# Microcontroller.net
KiCad netlist of a schematic drawn in Altium Designer
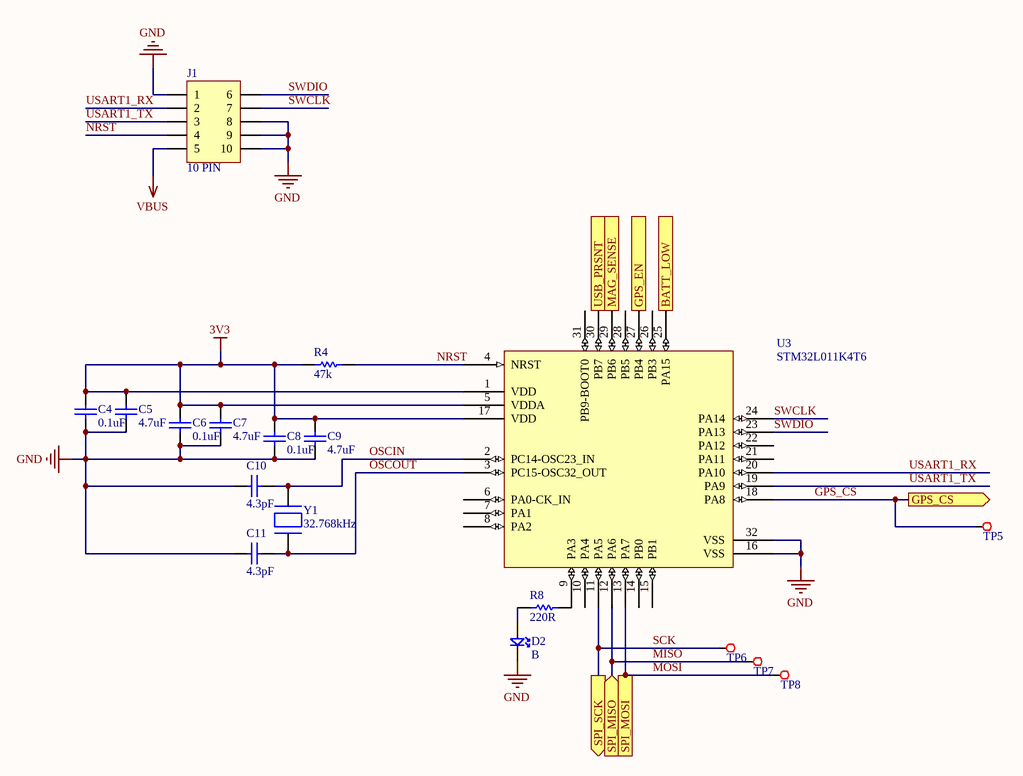
[diagram p0: Microcontroller.SchDoc]

(export (version "E")
  (design (tool "Eeschema 10.0.6"))
  (components
    (comp (ref "C4")
      (value "0.1uF")
      (footprint "0603CAP")
      (description "0603 Ceramic Chip Capacitor - Standard")
      (fields (field (name "Comment") "C0603"))
      (libsource (lib "Standard Components") (part "C0603"))
    )
    (comp (ref "C5")
      (value "4.7uF")
      (footprint "0603CAP")
      (description "0603 Ceramic Chip Capacitor - Standard")
      (fields (field (name "Comment") "C0603"))
      (libsource (lib "Standard Components") (part "C0603"))
    )
    (comp (ref "C6")
      (value "0.1uF")
      (footprint "0603CAP")
      (description "0603 Ceramic Chip Capacitor - Standard")
      (fields (field (name "Comment") "C0603"))
      (libsource (lib "Standard Components") (part "C0603"))
    )
    (comp (ref "C7")
      (value "4.7uF")
      (footprint "0603CAP")
      (description "0603 Ceramic Chip Capacitor - Standard")
      (fields (field (name "Comment") "C0603"))
      (libsource (lib "Standard Components") (part "C0603"))
    )
    (comp (ref "C8")
      (value "0.1uF")
      (footprint "0603CAP")
      (description "0603 Ceramic Chip Capacitor - Standard")
      (fields (field (name "Comment") "C0603"))
      (libsource (lib "Standard Components") (part "C0603"))
    )
    (comp (ref "C9")
      (value "4.7uF")
      (footprint "0603CAP")
      (description "0603 Ceramic Chip Capacitor - Standard")
      (fields (field (name "Comment") "C0603"))
      (libsource (lib "Standard Components") (part "C0603"))
    )
    (comp (ref "C10")
      (value "4.3pF")
      (footprint "0402cap")
      (description "0402 Ceramic Chip Capacitor - Standard")
      (fields (field (name "Comment") "C0402"))
      (libsource (lib "lib-Standard") (part "C0402"))
    )
    (comp (ref "C11")
      (value "4.3pF")
      (footprint "0402cap")
      (description "0402 Ceramic Chip Capacitor - Standard")
      (fields (field (name "Comment") "C0402"))
      (libsource (lib "lib-Standard") (part "C0402"))
    )
    (comp (ref "D2")
      (value "B")
      (footprint "0603DDE")
      (description "0603 SMD LED")
      (fields (field (name "Comment") "D0603"))
      (libsource (lib "lib-Standard") (part "D0603"))
    )
    (comp (ref "J1")
      (value "10 PIN")
      (footprint "FTSH-105-01-F-D-K")
      (description "10 Pin Programming Header")
      (libsource (lib "lib-Connectors") (part "FTSH-105-01-F-D-K"))
    )
    (comp (ref "R4")
      (value "47k")
      (footprint "0402RES")
      (description "0402 Chip Resistor - Standard")
      (fields (field (name "Comment") "R0402"))
      (libsource (lib "Standard Components") (part "R0402"))
    )
    (comp (ref "R8")
      (value "220R")
      (footprint "0402RES")
      (description "0402 Chip Resistor - Standard")
      (fields (field (name "Comment") "R0402"))
      (libsource (lib "Chip Resistor") (part "R0402"))
    )
    (comp (ref "TP5")
      (value "TESTPOINT")
      (footprint "TP R25")
      (description "0.025\" Round Test Point")
      (fields (field (name "PART NUMBER") "1613"))
      (libsource (lib "Standard Components") (part "TP25"))
    )
    (comp (ref "TP6")
      (value "TESTPOINT")
      (footprint "TP R35 TH15")
      (description "0.035\"/0.015\" Thru Hole Test Point")
      (fields (field (name "PART NUMBER") "1617"))
      (libsource (lib "lib-Standard") (part "TP35TH10"))
    )
    (comp (ref "TP7")
      (value "TESTPOINT")
      (footprint "TP R35 TH15")
      (description "0.035\"/0.015\" Thru Hole Test Point")
      (fields (field (name "PART NUMBER") "1617"))
      (libsource (lib "lib-Standard") (part "TP35TH10"))
    )
    (comp (ref "TP8")
      (value "TESTPOINT")
      (footprint "TP R35 TH15")
      (description "0.035\"/0.015\" Thru Hole Test Point")
      (fields (field (name "PART NUMBER") "1617"))
      (libsource (lib "lib-Standard") (part "TP35TH10"))
    )
    (comp (ref "U3")
      (value "STM32L011K4T6")
      (footprint "LQFP32")
      (description "STMicro ARM M0+ Microcontroller")
      (libsource (lib "lib-Microcontrollers") (part "STM32L011K4T6"))
    )
    (comp (ref "Y1")
      (value "32.768kHz")
      (footprint "0.126\" L x 0.061\" W (2 PAD)")
      (description "NDK RTC 12.5pF Crystal SMD")
      (libsource (lib "lib-Crystals") (part "NX3215SA-32.768K-STD-MUA-8"))
    )
  )
  (nets
    (net (code "1") (name "/BATT_LOW") (class "Default")
      (node (ref "U3") (pin "25") (pinfunction "PA15_25") (pintype "bidirectional"))
    )
    (net (code "2") (name "/GPS_CS") (class "Default")
      (node (ref "TP5") (pin "1") (pinfunction "1_1") (pintype "passive"))
      (node (ref "U3") (pin "18") (pinfunction "PA8_18") (pintype "bidirectional"))
    )
    (net (code "3") (name "/GPS_EN") (class "Default")
      (node (ref "U3") (pin "27") (pinfunction "PB4_27") (pintype "bidirectional"))
    )
    (net (code "4") (name "/MAG_SENSE") (class "Default")
      (node (ref "U3") (pin "29") (pinfunction "PB6_29") (pintype "bidirectional"))
    )
    (net (code "5") (name "/MISO") (class "Default")
      (node (ref "TP7") (pin "1") (pinfunction "1_1") (pintype "passive"))
      (node (ref "U3") (pin "12") (pinfunction "PA6_12") (pintype "bidirectional"))
    )
    (net (code "6") (name "/MOSI") (class "Default")
      (node (ref "TP8") (pin "1") (pinfunction "1_1") (pintype "passive"))
      (node (ref "U3") (pin "13") (pinfunction "PA7_13") (pintype "bidirectional"))
    )
    (net (code "7") (name "/NRST") (class "Default")
      (node (ref "J1") (pin "4") (pinfunction "4_4") (pintype "passive"))
      (node (ref "R4") (pin "2") (pinfunction "2_2") (pintype "passive"))
      (node (ref "U3") (pin "4") (pinfunction "NRST_4") (pintype "input"))
    )
    (net (code "8") (name "/OSCIN") (class "Default")
      (node (ref "C10") (pin "2") (pinfunction "2_2") (pintype "passive"))
      (node (ref "U3") (pin "2") (pinfunction "PC14-OSC23_IN_2") (pintype "bidirectional"))
      (node (ref "Y1") (pin "2") (pinfunction "2_2") (pintype "passive"))
    )
    (net (code "9") (name "/OSCOUT") (class "Default")
      (node (ref "C11") (pin "2") (pinfunction "2_2") (pintype "passive"))
      (node (ref "U3") (pin "3") (pinfunction "PC15-OSC32_OUT_3") (pintype "bidirectional"))
      (node (ref "Y1") (pin "1") (pinfunction "1_1") (pintype "passive"))
    )
    (net (code "10") (name "/SCK") (class "Default")
      (node (ref "TP6") (pin "1") (pinfunction "1_1") (pintype "passive"))
      (node (ref "U3") (pin "11") (pinfunction "PA5_11") (pintype "bidirectional"))
    )
    (net (code "11") (name "/SWCLK") (class "Default")
      (node (ref "J1") (pin "7") (pinfunction "7_7") (pintype "passive"))
      (node (ref "U3") (pin "24") (pinfunction "PA14_24") (pintype "bidirectional"))
    )
    (net (code "12") (name "/SWDIO") (class "Default")
      (node (ref "J1") (pin "6") (pinfunction "6_6") (pintype "passive"))
      (node (ref "U3") (pin "23") (pinfunction "PA13_23") (pintype "bidirectional"))
    )
    (net (code "13") (name "/USART1_RX") (class "Default")
      (node (ref "J1") (pin "2") (pinfunction "2_2") (pintype "passive"))
      (node (ref "U3") (pin "20") (pinfunction "PA10_20") (pintype "bidirectional"))
    )
    (net (code "14") (name "/USART1_TX") (class "Default")
      (node (ref "J1") (pin "3") (pinfunction "3_3") (pintype "passive"))
      (node (ref "U3") (pin "19") (pinfunction "PA9_19") (pintype "bidirectional"))
    )
    (net (code "15") (name "/USB_PRSNT") (class "Default")
      (node (ref "U3") (pin "30") (pinfunction "PB7_30") (pintype "bidirectional"))
    )
    (net (code "16") (name "3V3") (class "Default")
      (node (ref "C4") (pin "2") (pinfunction "2_2") (pintype "passive"))
      (node (ref "C5") (pin "2") (pinfunction "2_2") (pintype "passive"))
      (node (ref "C6") (pin "2") (pinfunction "2_2") (pintype "passive"))
      (node (ref "C7") (pin "2") (pinfunction "2_2") (pintype "passive"))
      (node (ref "C8") (pin "2") (pinfunction "2_2") (pintype "passive"))
      (node (ref "C9") (pin "2") (pinfunction "2_2") (pintype "passive"))
      (node (ref "R4") (pin "1") (pinfunction "1_1") (pintype "passive"))
      (node (ref "U3") (pin "1") (pinfunction "VDD_1") (pintype "power_in"))
      (node (ref "U3") (pin "17") (pinfunction "VDD_17") (pintype "power_in"))
      (node (ref "U3") (pin "5") (pinfunction "VDDA_5") (pintype "power_in"))
    )
    (net (code "17") (name "GND") (class "Default")
      (node (ref "C10") (pin "1") (pinfunction "1_1") (pintype "passive"))
      (node (ref "C11") (pin "1") (pinfunction "1_1") (pintype "passive"))
      (node (ref "C4") (pin "1") (pinfunction "1_1") (pintype "passive"))
      (node (ref "C5") (pin "1") (pinfunction "1_1") (pintype "passive"))
      (node (ref "C6") (pin "1") (pinfunction "1_1") (pintype "passive"))
      (node (ref "C7") (pin "1") (pinfunction "1_1") (pintype "passive"))
      (node (ref "C8") (pin "1") (pinfunction "1_1") (pintype "passive"))
      (node (ref "C9") (pin "1") (pinfunction "1_1") (pintype "passive"))
      (node (ref "D2") (pin "2") (pinfunction "2_2") (pintype "passive"))
      (node (ref "J1") (pin "1") (pinfunction "1_1") (pintype "passive"))
      (node (ref "J1") (pin "10") (pinfunction "10_10") (pintype "passive"))
      (node (ref "J1") (pin "8") (pinfunction "8_8") (pintype "passive"))
      (node (ref "J1") (pin "9") (pinfunction "9_9") (pintype "passive"))
      (node (ref "U3") (pin "16") (pinfunction "VSS_16") (pintype "power_in"))
      (node (ref "U3") (pin "32") (pinfunction "VSS_32") (pintype "power_in"))
    )
    (net (code "18") (name "Net-(D2-Pad1)") (class "Default")
      (node (ref "D2") (pin "1") (pinfunction "1_1") (pintype "passive"))
      (node (ref "R8") (pin "1") (pinfunction "1_1") (pintype "passive"))
    )
    (net (code "19") (name "Net-(U3-PA3)") (class "Default")
      (node (ref "R8") (pin "2") (pinfunction "2_2") (pintype "passive"))
      (node (ref "U3") (pin "9") (pinfunction "PA3_9") (pintype "bidirectional"))
    )
    (net (code "20") (name "VBUS") (class "Default")
      (node (ref "J1") (pin "5") (pinfunction "5_5") (pintype "passive"))
    )
    (net (code "21") (name "unconnected-(U3-PA0-CK_IN-Pad6)") (class "Default")
      (node (ref "U3") (pin "6") (pinfunction "PA0-CK_IN_6") (pintype "bidirectional"))
    )
    (net (code "22") (name "unconnected-(U3-PA1-Pad7)") (class "Default")
      (node (ref "U3") (pin "7") (pinfunction "PA1_7") (pintype "bidirectional"))
    )
    (net (code "23") (name "unconnected-(U3-PA2-Pad8)") (class "Default")
      (node (ref "U3") (pin "8") (pinfunction "PA2_8") (pintype "bidirectional"))
    )
    (net (code "24") (name "unconnected-(U3-PA4-Pad10)") (class "Default")
      (node (ref "U3") (pin "10") (pinfunction "PA4_10") (pintype "bidirectional"))
    )
    (net (code "25") (name "unconnected-(U3-PA11-Pad21)") (class "Default")
      (node (ref "U3") (pin "21") (pinfunction "PA11_21") (pintype "bidirectional"))
    )
    (net (code "26") (name "unconnected-(U3-PA12-Pad22)") (class "Default")
      (node (ref "U3") (pin "22") (pinfunction "PA12_22") (pintype "bidirectional"))
    )
    (net (code "27") (name "unconnected-(U3-PB0-Pad14)") (class "Default")
      (node (ref "U3") (pin "14") (pinfunction "PB0_14") (pintype "bidirectional"))
    )
    (net (code "28") (name "unconnected-(U3-PB1-Pad15)") (class "Default")
      (node (ref "U3") (pin "15") (pinfunction "PB1_15") (pintype "bidirectional"))
    )
    (net (code "29") (name "unconnected-(U3-PB3-Pad26)") (class "Default")
      (node (ref "U3") (pin "26") (pinfunction "PB3_26") (pintype "bidirectional"))
    )
    (net (code "30") (name "unconnected-(U3-PB5-Pad28)") (class "Default")
      (node (ref "U3") (pin "28") (pinfunction "PB5_28") (pintype "bidirectional"))
    )
    (net (code "31") (name "unconnected-(U3-PB9-BOOT0-Pad31)") (class "Default")
      (node (ref "U3") (pin "31") (pinfunction "PB9-BOOT0_31") (pintype "bidirectional"))
    )
  )
)
